# sfp.net
KiCad netlist of a schematic drawn in Altium Designer
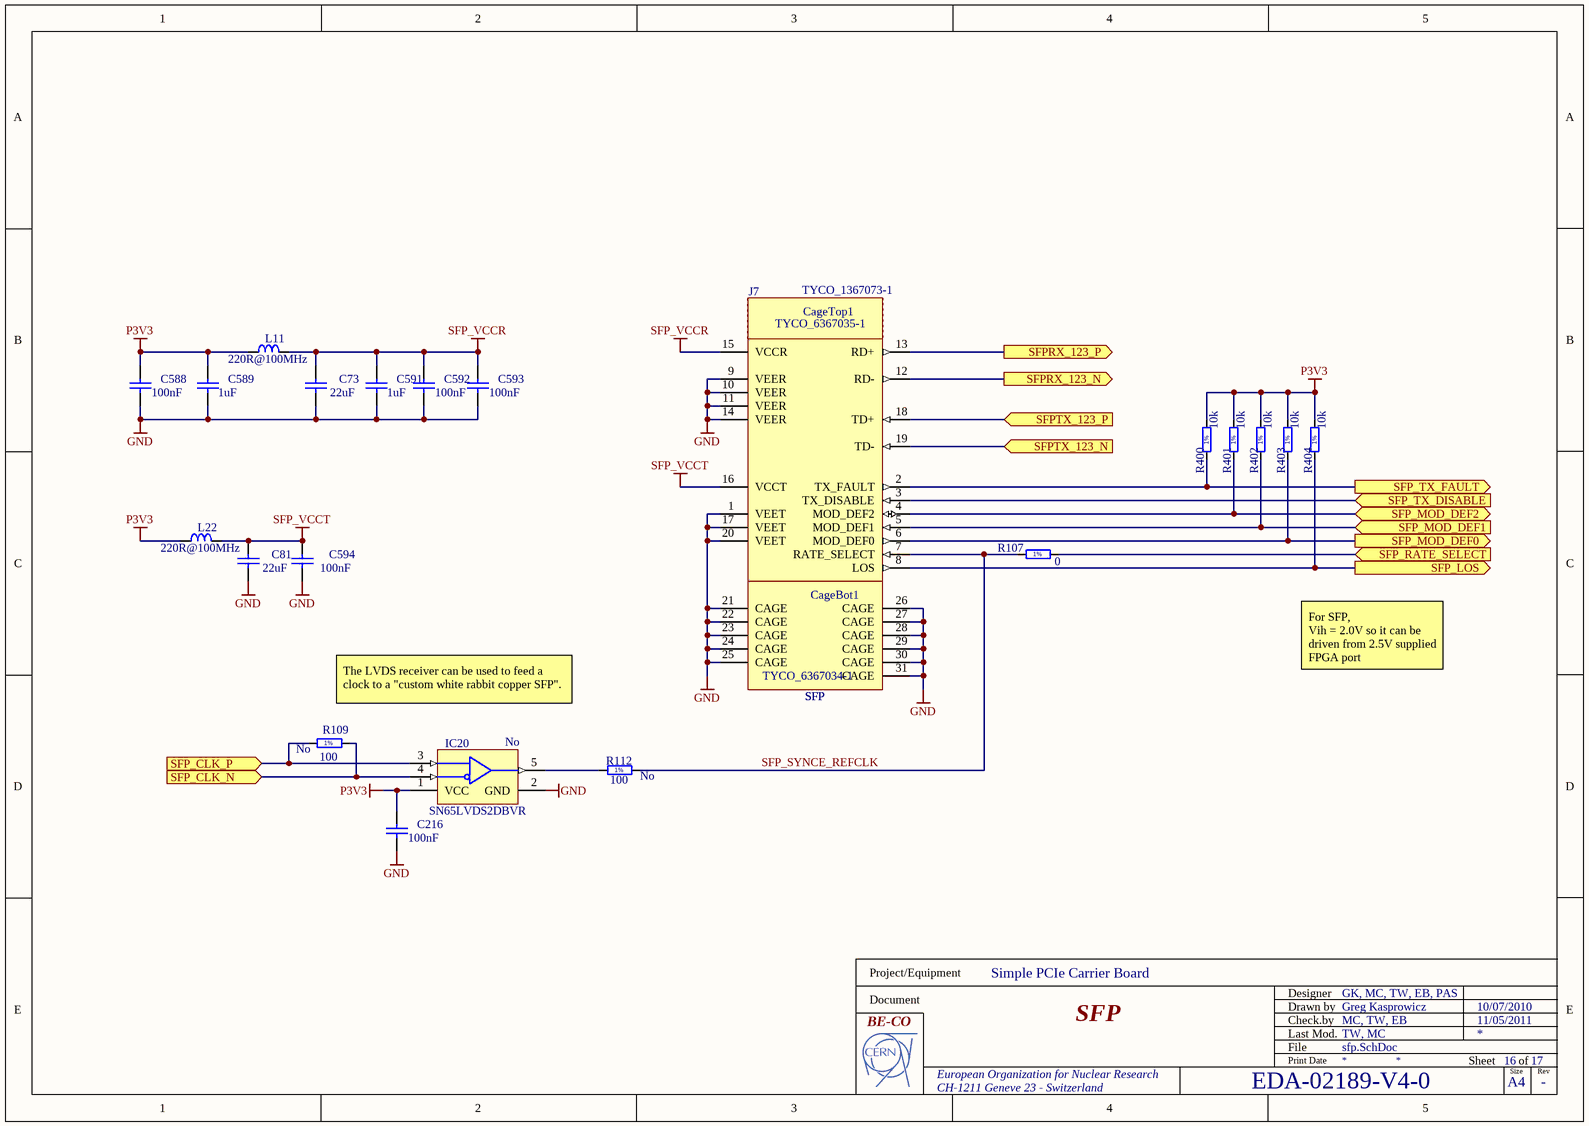
[diagram p0: sfp.SchDoc]

(export (version "E")
  (design (tool "Eeschema 10.0.6"))
  (components
    (comp (ref "C73")
      (value "22uF")
      (footprint "CAPC3216X180N")
      (description "Non-polarised capacitor")
      (fields
        (field (name "PART NUMBER") "CC1206_22UF_10V_10%_X7R")
        (field (name "VOLTAGE") "10V")
        (field (name "AUTHOR") "CERN DEM JLC")
      )
      (libsource (lib "Capacitors") (part "Capacitor - non polarized"))
    )
    (comp (ref "C81")
      (value "22uF")
      (footprint "CAPC3216X180N")
      (description "Non-polarised capacitor")
      (fields
        (field (name "PART NUMBER") "CC1206_22UF_10V_10%_X7R")
        (field (name "VOLTAGE") "10V")
        (field (name "AUTHOR") "CERN DEM JLC")
      )
      (libsource (lib "Capacitors") (part "Capacitor - non polarized"))
    )
    (comp (ref "C216")
      (value "100nF")
      (footprint "CAPC1608X87N")
      (description "Non-polarised capacitor")
      (fields
        (field (name "PART NUMBER") "CC0603_100NF_50V_10%_X7R")
        (field (name "VOLTAGE") "50V")
        (field (name "AUTHOR") "CERN DEM JLC")
      )
      (libsource (lib "Capacitors") (part "Capacitor - non polarized"))
    )
    (comp (ref "C588")
      (value "100nF")
      (footprint "CAPC1608X87N")
      (description "Non-polarised capacitor")
      (fields
        (field (name "PART NUMBER") "CC0603_100NF_50V_10%_X7R")
        (field (name "VOLTAGE") "50V")
        (field (name "AUTHOR") "CERN DEM JLC")
      )
      (libsource (lib "Capacitors") (part "Capacitor - non polarized"))
    )
    (comp (ref "C589")
      (value "1uF")
      (footprint "CAPC1608X87N")
      (description "Non-polarised capacitor")
      (fields
        (field (name "PART NUMBER") "CC0603_1UF_16V_10%_X7R")
        (field (name "VOLTAGE") "16V")
        (field (name "AUTHOR") "CERN DEM JLC")
      )
      (libsource (lib "Capacitors") (part "Capacitor - non polarized"))
    )
    (comp (ref "C591")
      (value "1uF")
      (footprint "CAPC1608X87N")
      (description "Non-polarised capacitor")
      (fields
        (field (name "PART NUMBER") "CC0603_1UF_16V_10%_X7R")
        (field (name "VOLTAGE") "16V")
        (field (name "AUTHOR") "CERN DEM JLC")
      )
      (libsource (lib "Capacitors") (part "Capacitor - non polarized"))
    )
    (comp (ref "C592")
      (value "100nF")
      (footprint "CAPC1608X87N")
      (description "Non-polarised capacitor")
      (fields
        (field (name "PART NUMBER") "CC0603_100NF_50V_10%_X7R")
        (field (name "VOLTAGE") "50V")
        (field (name "AUTHOR") "CERN DEM JLC")
      )
      (libsource (lib "Capacitors") (part "Capacitor - non polarized"))
    )
    (comp (ref "C593")
      (value "100nF")
      (footprint "CAPC1608X87N")
      (description "Non-polarised capacitor")
      (fields
        (field (name "PART NUMBER") "CC0603_100NF_50V_10%_X7R")
        (field (name "VOLTAGE") "50V")
        (field (name "AUTHOR") "CERN DEM JLC")
      )
      (libsource (lib "Capacitors") (part "Capacitor - non polarized"))
    )
    (comp (ref "C594")
      (value "100nF")
      (footprint "CAPC1608X87N")
      (description "Non-polarised capacitor")
      (fields
        (field (name "PART NUMBER") "CC0603_100NF_50V_10%_X7R")
        (field (name "VOLTAGE") "50V")
        (field (name "AUTHOR") "CERN DEM JLC")
      )
      (libsource (lib "Capacitors") (part "Capacitor - non polarized"))
    )
    (comp (ref "CageBot1")
      (value "SFP")
      (footprint "TYCO_6367034-1")
      (description "SFP  Cage Bottom (Small Form-factor Pluggable)")
      (fields
        (field (name "PART NUMBER") "TYCO_6367034-1")
        (field (name "MANUFACTURER") "TYCO ELECTRONICS")
        (field (name "MANUFACTURER PART NUMBER") "TYCO_6367034-1")
        (field (name "AUTHOR") "CERN DEM JLC")
      )
      (libsource (lib "Connectors") (part "SFPx1_Cage Bottom"))
    )
    (comp (ref "CageTop1")
      (value "SFP")
      (footprint "TYCO_6367035-1")
      (description "SFP  Cage Top (Small Form-factor Pluggable)")
      (fields
        (field (name "PART NUMBER") "TYCO_6367035-1")
        (field (name "MANUFACTURER") "TYCO ELECTRONICS")
        (field (name "MANUFACTURER PART NUMBER") "TYCO_6367035-1")
        (field (name "AUTHOR") "CERN DEM JLC")
      )
      (libsource (lib "Connectors") (part "SFPx1_Cage Top"))
    )
    (comp (ref "IC20")
      (value "SN65LVDS2DBVR")
      (footprint "SOT95P280X145-5N")
      (description "High-Speed Differential Line Receiver")
      (fields
        (field (name "MANUFACTURER") "TEXAS INSTRUMENTS")
        (field (name "MOUNTED") "No")
        (field (name "AUTHOR") "CERN DEM JLC")
      )
      (libsource (lib "ICs And Semiconductors") (part "SN65LVDS2DBVR"))
    )
    (comp (ref "J7")
      (value "SFP")
      (footprint "TYCO_1367073-1")
      (description "20 Position SFP  Connector (Small Form-factor Pluggable)")
      (fields
        (field (name "PART NUMBER") "TYCO_1367073-1")
        (field (name "MANUFACTURER") "TYCO ELECTRONICS")
        (field (name "MANUFACTURER PART NUMBER") "1367073-1")
        (field (name "AUTHOR") "CERN DEM JLC")
      )
      (libsource (lib "Connectors") (part "SFPx1"))
    )
    (comp (ref "L11")
      (value "220R@100MHz")
      (footprint "INDC2012X105N")
      (description "Inductor")
      (fields
        (field (name "PART NUMBER") "IND0805_MURATA_BLM21PG221SN1D")
        (field (name "POWER") "2A")
        (field (name "AUTHOR") "CERN DEM JLC")
      )
      (libsource (lib "Inductors & Transformers") (part "Inductor"))
    )
    (comp (ref "L22")
      (value "220R@100MHz")
      (footprint "INDC2012X105N")
      (description "Inductor")
      (fields
        (field (name "PART NUMBER") "IND0805_MURATA_BLM21PG221SN1D")
        (field (name "POWER") "2A")
        (field (name "AUTHOR") "CERN DEM JLC")
      )
      (libsource (lib "Inductors & Transformers") (part "Inductor"))
    )
    (comp (ref "R107")
      (value "0")
      (footprint "RESC1608X55N")
      (description "Resistor - 1%")
      (fields
        (field (name "PART NUMBER") "R0603_0R_JUMPER")
        (field (name "MANUFACTURER") "GENERIC")
        (field (name "AUTHOR") "CERN DEM JLC")
      )
      (libsource (lib "Resistors") (part "Resistor - 1%"))
    )
    (comp (ref "R109")
      (value "100")
      (footprint "RESC1608X55N")
      (description "Resistor - 1%")
      (fields
        (field (name "PART NUMBER") "R0603_100R_1%_0.1W_100PPM")
        (field (name "POWER") "0.1W")
        (field (name "MOUNTED") "No")
        (field (name "AUTHOR") "CERN DEM JLC")
      )
      (libsource (lib "Resistors") (part "Resistor - 1%"))
    )
    (comp (ref "R112")
      (value "100")
      (footprint "RESC1608X55N")
      (description "Resistor - 1%")
      (fields
        (field (name "PART NUMBER") "R0603_100R_1%_0.1W_100PPM")
        (field (name "POWER") "0.1W")
        (field (name "MOUNTED") "No")
        (field (name "AUTHOR") "CERN DEM JLC")
      )
      (libsource (lib "Resistors") (part "Resistor - 1%"))
    )
    (comp (ref "R400")
      (value "10k")
      (footprint "RESC1608X55N")
      (description "Resistor - 1%")
      (fields
        (field (name "PART NUMBER") "R0603_10K_1%_0.1W_100PPM")
        (field (name "POWER") "0.1W")
        (field (name "AUTHOR") "CERN DEM JLC")
      )
      (libsource (lib "Resistors") (part "Resistor - 1%"))
    )
    (comp (ref "R401")
      (value "10k")
      (footprint "RESC1608X55N")
      (description "Resistor - 1%")
      (fields
        (field (name "PART NUMBER") "R0603_10K_1%_0.1W_100PPM")
        (field (name "POWER") "0.1W")
        (field (name "AUTHOR") "CERN DEM JLC")
      )
      (libsource (lib "Resistors") (part "Resistor - 1%"))
    )
    (comp (ref "R402")
      (value "10k")
      (footprint "RESC1608X55N")
      (description "Resistor - 1%")
      (fields
        (field (name "PART NUMBER") "R0603_10K_1%_0.1W_100PPM")
        (field (name "POWER") "0.1W")
        (field (name "AUTHOR") "CERN DEM JLC")
      )
      (libsource (lib "Resistors") (part "Resistor - 1%"))
    )
    (comp (ref "R403")
      (value "10k")
      (footprint "RESC1608X55N")
      (description "Resistor - 1%")
      (fields
        (field (name "PART NUMBER") "R0603_10K_1%_0.1W_100PPM")
        (field (name "POWER") "0.1W")
        (field (name "AUTHOR") "CERN DEM JLC")
      )
      (libsource (lib "Resistors") (part "Resistor - 1%"))
    )
    (comp (ref "R404")
      (value "10k")
      (footprint "RESC1608X55N")
      (description "Resistor - 1%")
      (fields
        (field (name "PART NUMBER") "R0603_10K_1%_0.1W_100PPM")
        (field (name "POWER") "0.1W")
        (field (name "AUTHOR") "CERN DEM JLC")
      )
      (libsource (lib "Resistors") (part "Resistor - 1%"))
    )
  )
  (nets
    (net (code "1") (name "/SFPRX_123_N") (class "Default")
      (node (ref "J7") (pin "12") (pinfunction "RD-_12") (pintype "output"))
    )
    (net (code "2") (name "/SFPRX_123_P") (class "Default")
      (node (ref "J7") (pin "13") (pinfunction "RD+_13") (pintype "output"))
    )
    (net (code "3") (name "/SFPTX_123_N") (class "Default")
      (node (ref "J7") (pin "19") (pinfunction "TD-_19") (pintype "input"))
    )
    (net (code "4") (name "/SFPTX_123_P") (class "Default")
      (node (ref "J7") (pin "18") (pinfunction "TD+_18") (pintype "input"))
    )
    (net (code "5") (name "/SFP_CLK_N") (class "Default")
      (node (ref "IC20") (pin "4") (pinfunction "B_4") (pintype "input"))
      (node (ref "R109") (pin "2") (pinfunction "2_2") (pintype "passive"))
    )
    (net (code "6") (name "/SFP_CLK_P") (class "Default")
      (node (ref "IC20") (pin "3") (pinfunction "A_3") (pintype "input"))
      (node (ref "R109") (pin "1") (pinfunction "1_1") (pintype "passive"))
    )
    (net (code "7") (name "/SFP_LOS") (class "Default")
      (node (ref "J7") (pin "8") (pinfunction "LOS_8") (pintype "output"))
      (node (ref "R404") (pin "1") (pinfunction "1_1") (pintype "passive"))
    )
    (net (code "8") (name "/SFP_MOD_DEF0") (class "Default")
      (node (ref "J7") (pin "6") (pinfunction "MOD_DEF0_6") (pintype "output"))
      (node (ref "R403") (pin "1") (pinfunction "1_1") (pintype "passive"))
    )
    (net (code "9") (name "/SFP_MOD_DEF1") (class "Default")
      (node (ref "J7") (pin "5") (pinfunction "MOD_DEF1_5") (pintype "input"))
      (node (ref "R402") (pin "1") (pinfunction "1_1") (pintype "passive"))
    )
    (net (code "10") (name "/SFP_MOD_DEF2") (class "Default")
      (node (ref "J7") (pin "4") (pinfunction "MOD_DEF2_4") (pintype "bidirectional"))
      (node (ref "R401") (pin "1") (pinfunction "1_1") (pintype "passive"))
    )
    (net (code "11") (name "/SFP_RATE_SELECT") (class "Default")
      (node (ref "R107") (pin "2") (pinfunction "2_2") (pintype "passive"))
    )
    (net (code "12") (name "/SFP_SYNCE_REFCLK") (class "Default")
      (node (ref "J7") (pin "7") (pinfunction "RATE_SELECT_7") (pintype "input"))
      (node (ref "R107") (pin "1") (pinfunction "1_1") (pintype "passive"))
      (node (ref "R112") (pin "2") (pinfunction "2_2") (pintype "passive"))
    )
    (net (code "13") (name "/SFP_TX_DISABLE") (class "Default")
      (node (ref "J7") (pin "3") (pinfunction "TX_DISABLE_3") (pintype "input"))
    )
    (net (code "14") (name "/SFP_TX_FAULT") (class "Default")
      (node (ref "J7") (pin "2") (pinfunction "TX_FAULT_2") (pintype "output"))
      (node (ref "R400") (pin "1") (pinfunction "1_1") (pintype "passive"))
    )
    (net (code "15") (name "GND") (class "Default")
      (node (ref "C216") (pin "2") (pinfunction "2_2") (pintype "passive"))
      (node (ref "C588") (pin "1") (pinfunction "1_1") (pintype "passive"))
      (node (ref "C589") (pin "1") (pinfunction "1_1") (pintype "passive"))
      (node (ref "C591") (pin "1") (pinfunction "1_1") (pintype "passive"))
      (node (ref "C592") (pin "1") (pinfunction "1_1") (pintype "passive"))
      (node (ref "C593") (pin "1") (pinfunction "1_1") (pintype "passive"))
      (node (ref "C594") (pin "1") (pinfunction "1_1") (pintype "passive"))
      (node (ref "C73") (pin "1") (pinfunction "1_1") (pintype "passive"))
      (node (ref "C81") (pin "1") (pinfunction "1_1") (pintype "passive"))
      (node (ref "CageBot1") (pin "21") (pinfunction "CAGE_21") (pintype "power_in"))
      (node (ref "CageBot1") (pin "22") (pinfunction "CAGE_22") (pintype "power_in"))
      (node (ref "CageBot1") (pin "23") (pinfunction "CAGE_23") (pintype "power_in"))
      (node (ref "CageBot1") (pin "24") (pinfunction "CAGE_24") (pintype "power_in"))
      (node (ref "CageBot1") (pin "25") (pinfunction "CAGE_25") (pintype "power_in"))
      (node (ref "CageBot1") (pin "26") (pinfunction "CAGE_26") (pintype "power_in"))
      (node (ref "CageBot1") (pin "27") (pinfunction "CAGE_27") (pintype "power_in"))
      (node (ref "CageBot1") (pin "28") (pinfunction "CAGE_28") (pintype "power_in"))
      (node (ref "CageBot1") (pin "29") (pinfunction "CAGE_29") (pintype "power_in"))
      (node (ref "CageBot1") (pin "30") (pinfunction "CAGE_30") (pintype "power_in"))
      (node (ref "CageBot1") (pin "31") (pinfunction "CAGE_31") (pintype "power_in"))
      (node (ref "IC20") (pin "2") (pinfunction "GND_2") (pintype "power_in"))
      (node (ref "J7") (pin "1") (pinfunction "VEET_1") (pintype "power_in"))
      (node (ref "J7") (pin "10") (pinfunction "VEER_10") (pintype "power_in"))
      (node (ref "J7") (pin "11") (pinfunction "VEER_11") (pintype "power_in"))
      (node (ref "J7") (pin "14") (pinfunction "VEER_14") (pintype "power_in"))
      (node (ref "J7") (pin "17") (pinfunction "VEET_17") (pintype "power_in"))
      (node (ref "J7") (pin "20") (pinfunction "VEET_20") (pintype "power_in"))
      (node (ref "J7") (pin "9") (pinfunction "VEER_9") (pintype "power_in"))
    )
    (net (code "16") (name "Net-(IC20-R)") (class "Default")
      (node (ref "IC20") (pin "5") (pinfunction "R_5") (pintype "output"))
      (node (ref "R112") (pin "1") (pinfunction "1_1") (pintype "passive"))
    )
    (net (code "17") (name "P3V3") (class "Default")
      (node (ref "C216") (pin "1") (pinfunction "1_1") (pintype "passive"))
      (node (ref "C588") (pin "2") (pinfunction "2_2") (pintype "passive"))
      (node (ref "C589") (pin "2") (pinfunction "2_2") (pintype "passive"))
      (node (ref "IC20") (pin "1") (pinfunction "VCC_1") (pintype "power_in"))
      (node (ref "L11") (pin "1") (pinfunction "1_1") (pintype "passive"))
      (node (ref "L22") (pin "1") (pinfunction "1_1") (pintype "passive"))
      (node (ref "R400") (pin "2") (pinfunction "2_2") (pintype "passive"))
      (node (ref "R401") (pin "2") (pinfunction "2_2") (pintype "passive"))
      (node (ref "R402") (pin "2") (pinfunction "2_2") (pintype "passive"))
      (node (ref "R403") (pin "2") (pinfunction "2_2") (pintype "passive"))
      (node (ref "R404") (pin "2") (pinfunction "2_2") (pintype "passive"))
    )
    (net (code "18") (name "SFP_VCCR") (class "Default")
      (node (ref "C591") (pin "2") (pinfunction "2_2") (pintype "passive"))
      (node (ref "C592") (pin "2") (pinfunction "2_2") (pintype "passive"))
      (node (ref "C593") (pin "2") (pinfunction "2_2") (pintype "passive"))
      (node (ref "C73") (pin "2") (pinfunction "2_2") (pintype "passive"))
      (node (ref "J7") (pin "15") (pinfunction "VCCR_15") (pintype "power_in"))
      (node (ref "L11") (pin "2") (pinfunction "2_2") (pintype "passive"))
    )
    (net (code "19") (name "SFP_VCCT") (class "Default")
      (node (ref "C594") (pin "2") (pinfunction "2_2") (pintype "passive"))
      (node (ref "C81") (pin "2") (pinfunction "2_2") (pintype "passive"))
      (node (ref "J7") (pin "16") (pinfunction "VCCT_16") (pintype "power_in"))
      (node (ref "L22") (pin "2") (pinfunction "2_2") (pintype "passive"))
    )
  )
)
